# Audio.net
KiCad netlist of a schematic drawn in Altium Designer
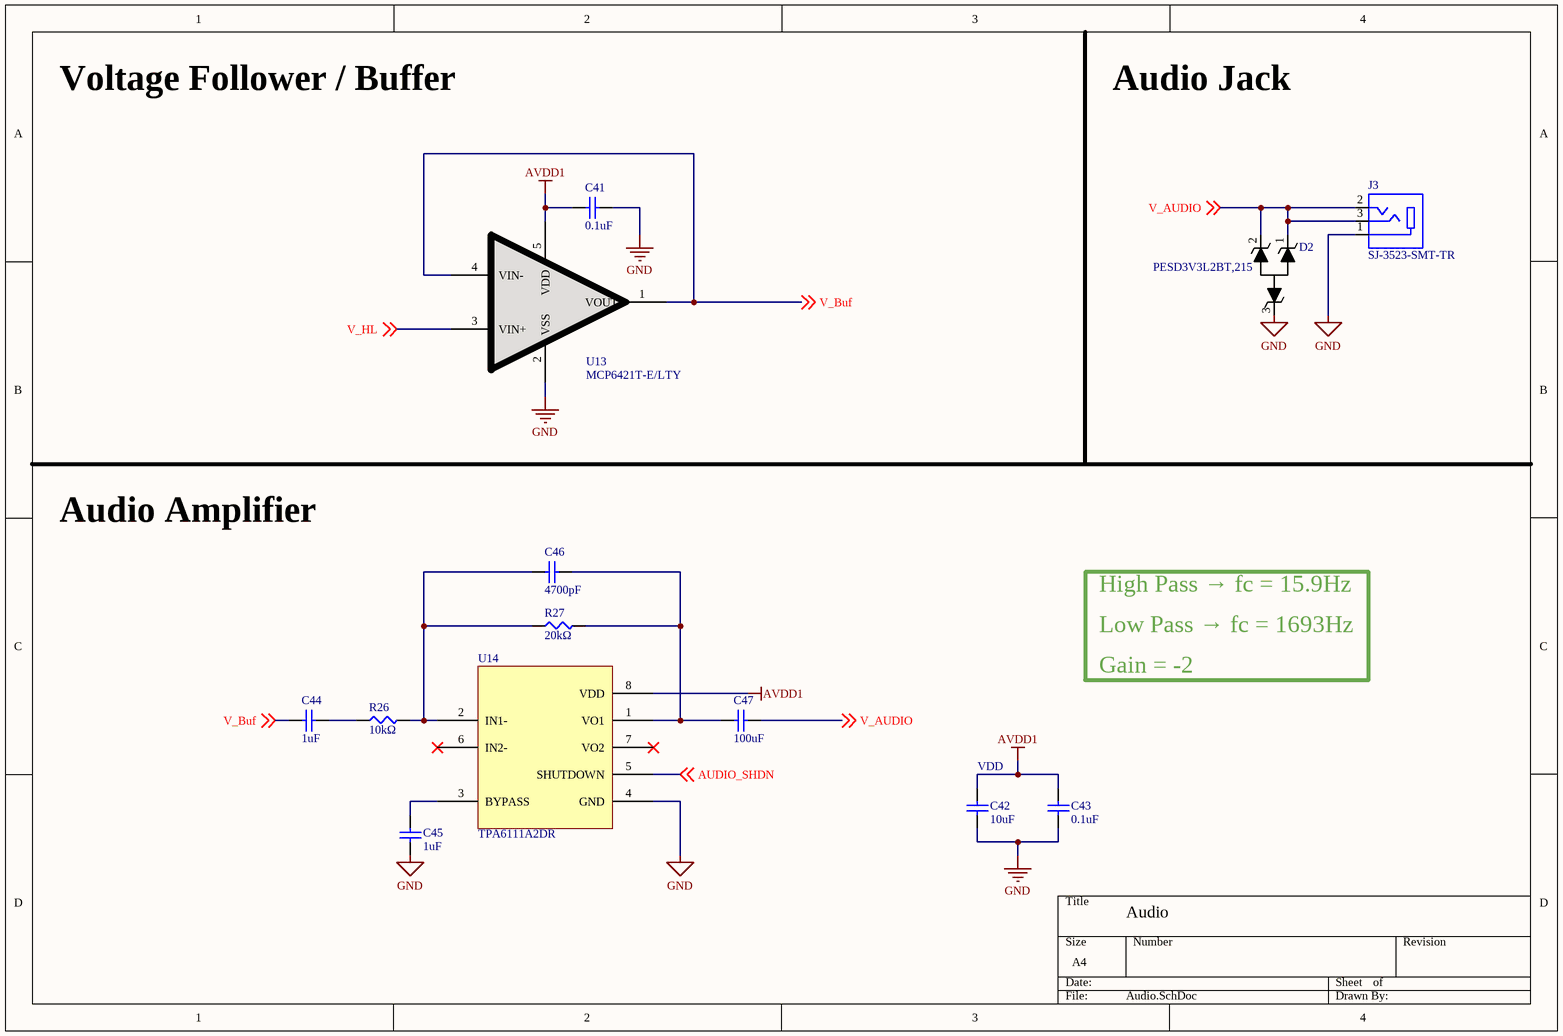
[diagram p0: Audio.SchDoc]

(export (version "E")
  (design (tool "Eeschema 10.0.6"))
  (components
    (comp (ref "C41")
      (value "0.1uF")
      (footprint "0402")
      (description "MLCC-0402")
      (libsource (lib "MLCC") (part "0402"))
    )
    (comp (ref "C42")
      (value "10uF")
      (footprint "0603")
      (description "MLCC-0603")
      (libsource (lib "MLCC") (part "0603"))
    )
    (comp (ref "C43")
      (value "0.1uF")
      (footprint "0402")
      (description "MLCC-0402")
      (libsource (lib "MLCC") (part "0402"))
    )
    (comp (ref "C44")
      (value "1uF")
      (footprint "0402")
      (description "MLCC-0402")
      (libsource (lib "MLCC") (part "0402"))
    )
    (comp (ref "C45")
      (value "1uF")
      (footprint "0402")
      (description "MLCC-0402")
      (libsource (lib "MLCC") (part "0402"))
    )
    (comp (ref "C46")
      (value "4700pF")
      (footprint "0402")
      (description "MLCC-0402")
      (libsource (lib "MLCC") (part "0402"))
    )
    (comp (ref "C47")
      (value "100uF")
      (footprint "1206")
      (description "MLCC-1206")
      (libsource (lib "MLCC") (part "1206"))
    )
    (comp (ref "D2")
      (value "PESD3V3L2BT,215")
      (footprint "SOT-23-3")
      (description "ESD Suppressors / TVS Diodes, 2 Channl. Breakdown 6.4V, Clamping Voltage 8V")
      (libsource (lib "PESDxL2BT") (part "PESD3V3L2BT,215"))
    )
    (comp (ref "J3")
      (value "SJ-3523-SMT-TR")
      (footprint "CUI_SJ-3523-SMT-TR")
      (description "3.5 mm, Stereo, Right Angle, Surface Mount _SMT_, Audio Jack Connector")
      (fields (field (name "MF") "CUI Devices"))
      (libsource (lib "SJ-3523-SMT-TR") (part "SJ-3523-SMT-TR"))
    )
    (comp (ref "R26")
      (value "10kΩ")
      (footprint "0402")
      (description "Resistor_SMD_0402")
      (fields (field (name "AUTHORBY") "yjlab"))
      (libsource (lib "Resistor") (part "0402"))
    )
    (comp (ref "R27")
      (value "20kΩ")
      (footprint "0402")
      (description "Resistor_SMD_0402")
      (fields (field (name "AUTHORBY") "yjlab"))
      (libsource (lib "Resistor") (part "0402"))
    )
    (comp (ref "U13")
      (value "MCP6421T-E/LTY")
      (footprint "SC-70-5")
      (description "4.4 µA/Amplifier, 90 kHz Op Amp")
      (libsource (lib "MCP642x") (part "MCP6421T-E/LTY"))
    )
    (comp (ref "U14")
      (value "TPA6111A2DR")
      (footprint "SOIC-8")
      (description "Audio Power Amp")
      (libsource (lib "TPA6111A2") (part "TPA6111A2DR"))
    )
  )
  (nets
    (net (code "1") (name "AUDIO_SHDN") (class "Default")
      (node (ref "U14") (pin "5") (pinfunction "SHUTDOWN_5") (pintype "passive"))
    )
    (net (code "2") (name "AVDD1") (class "Default")
      (node (ref "C41") (pin "1") (pinfunction "1_1") (pintype "passive"))
      (node (ref "C42") (pin "2") (pinfunction "2_2") (pintype "passive"))
      (node (ref "C43") (pin "1") (pinfunction "1_1") (pintype "passive"))
      (node (ref "U13") (pin "5") (pinfunction "VDD_5") (pintype "passive"))
      (node (ref "U14") (pin "8") (pinfunction "VDD_8") (pintype "passive"))
    )
    (net (code "3") (name "GND") (class "Default")
      (node (ref "C41") (pin "2") (pinfunction "2_2") (pintype "passive"))
      (node (ref "C42") (pin "1") (pinfunction "1_1") (pintype "passive"))
      (node (ref "C43") (pin "2") (pinfunction "2_2") (pintype "passive"))
      (node (ref "C45") (pin "1") (pinfunction "1_1") (pintype "passive"))
      (node (ref "D2") (pin "3") (pinfunction "3_3") (pintype "passive"))
      (node (ref "J3") (pin "1") (pinfunction "1_1") (pintype "passive"))
      (node (ref "U13") (pin "2") (pinfunction "VSS_2") (pintype "passive"))
      (node (ref "U14") (pin "4") (pinfunction "GND_4") (pintype "passive"))
    )
    (net (code "4") (name "Net-(C44-Pad2)") (class "Default")
      (node (ref "C44") (pin "2") (pinfunction "2_2") (pintype "passive"))
      (node (ref "R26") (pin "1") (pinfunction "1_1") (pintype "passive"))
    )
    (net (code "5") (name "Net-(U14-BYPASS)") (class "Default")
      (node (ref "C45") (pin "2") (pinfunction "2_2") (pintype "passive"))
      (node (ref "U14") (pin "3") (pinfunction "BYPASS_3") (pintype "passive"))
    )
    (net (code "6") (name "Net-(U14-IN1-)") (class "Default")
      (node (ref "C46") (pin "1") (pinfunction "1_1") (pintype "passive"))
      (node (ref "R26") (pin "2") (pinfunction "2_2") (pintype "passive"))
      (node (ref "R27") (pin "1") (pinfunction "1_1") (pintype "passive"))
      (node (ref "U14") (pin "2") (pinfunction "IN1-_2") (pintype "passive"))
    )
    (net (code "7") (name "Net-(U14-VO1)") (class "Default")
      (node (ref "C46") (pin "2") (pinfunction "2_2") (pintype "passive"))
      (node (ref "C47") (pin "1") (pinfunction "1_1") (pintype "passive"))
      (node (ref "R27") (pin "2") (pinfunction "2_2") (pintype "passive"))
      (node (ref "U14") (pin "1") (pinfunction "VO1_1") (pintype "passive"))
    )
    (net (code "8") (name "V_AUDIO") (class "Default")
      (node (ref "C47") (pin "2") (pinfunction "2_2") (pintype "passive"))
      (node (ref "D2") (pin "1") (pinfunction "1_1") (pintype "passive"))
      (node (ref "D2") (pin "2") (pinfunction "2_2") (pintype "passive"))
      (node (ref "J3") (pin "2") (pinfunction "2_2") (pintype "passive"))
      (node (ref "J3") (pin "3") (pinfunction "3_3") (pintype "passive"))
    )
    (net (code "9") (name "V_Buf") (class "Default")
      (node (ref "C44") (pin "1") (pinfunction "1_1") (pintype "passive"))
      (node (ref "U13") (pin "1") (pinfunction "VOUT_1") (pintype "passive"))
      (node (ref "U13") (pin "4") (pinfunction "VIN-_4") (pintype "passive"))
    )
    (net (code "10") (name "V_HL") (class "Default")
      (node (ref "U13") (pin "3") (pinfunction "VIN+_3") (pintype "passive"))
    )
    (net (code "11") (name "unconnected-(U14-IN2--Pad6)") (class "Default")
      (node (ref "U14") (pin "6") (pinfunction "IN2-_6") (pintype "passive+no_connect"))
    )
    (net (code "12") (name "unconnected-(U14-VO2-Pad7)") (class "Default")
      (node (ref "U14") (pin "7") (pinfunction "VO2_7") (pintype "passive+no_connect"))
    )
  )
)
